# 06_DRIVER.net
KiCad netlist of a schematic drawn in Altium Designer
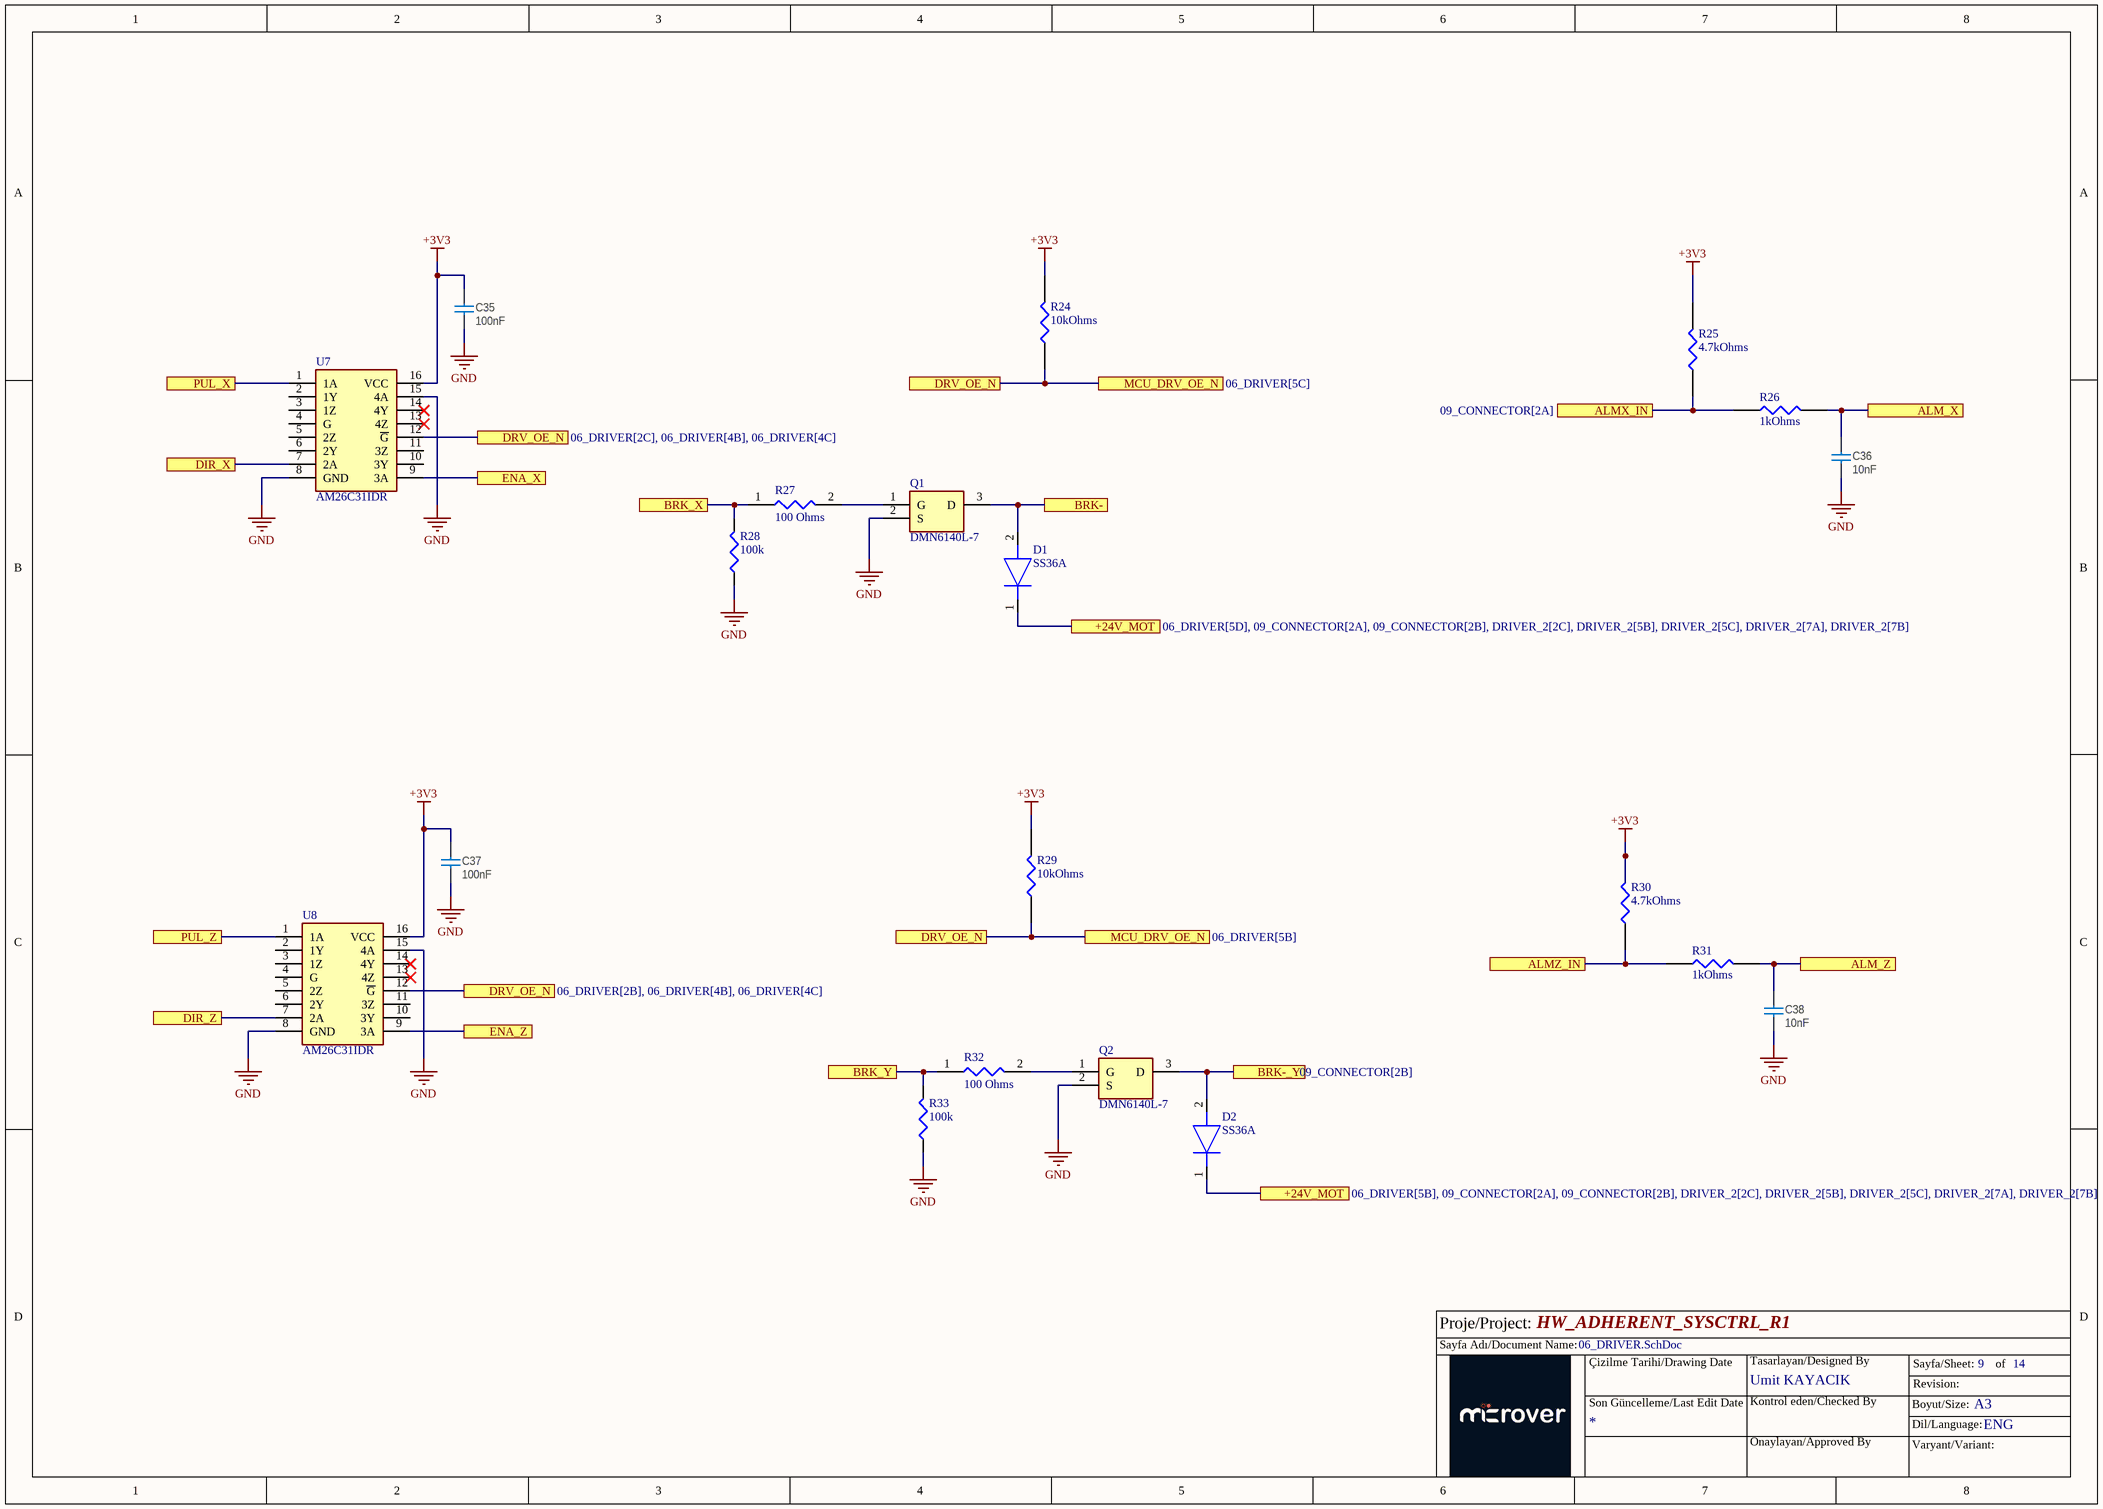
[diagram p0: 06_DRIVER.SchDoc]

(export (version "E")
  (design (tool "Eeschema 10.0.6"))
  (components
    (comp (ref "C35")
      (value "100nF")
      (footprint "CAPC0603X03L_C")
      (description "Capacitor, X5R, ±10%")
      (fields
        (field (name "PART NUMBER") "C0201-100n")
        (field (name "MANUFACTURER") "N.A.")
        (field (name "AUTHOR") "rsk")
      )
      (libsource (lib "HW_ADHERENT_SYSCTRL_R1_L1") (part "C0201-100n"))
    )
    (comp (ref "C36")
      (value "10nF")
      (footprint "CAPC0603X03L_C")
      (description "Capacitor, X7R, ±10%")
      (fields
        (field (name "PART NUMBER") "C0201-10n")
        (field (name "MANUFACTURER") "N.A.")
        (field (name "AUTHOR") "rsk")
      )
      (libsource (lib "HW_ADHERENT_SYSCTRL_R1_L1") (part "C0201-10n"))
    )
    (comp (ref "C37")
      (value "100nF")
      (footprint "CAPC0603X03L_C")
      (description "Capacitor, X5R, ±10%")
      (fields
        (field (name "PART NUMBER") "C0201-100n")
        (field (name "MANUFACTURER") "N.A.")
        (field (name "AUTHOR") "rsk")
      )
      (libsource (lib "HW_ADHERENT_SYSCTRL_R1_L1") (part "C0201-100n"))
    )
    (comp (ref "C38")
      (value "10nF")
      (footprint "CAPC0603X03L_C")
      (description "Capacitor, X7R, ±10%")
      (fields
        (field (name "PART NUMBER") "C0201-10n")
        (field (name "MANUFACTURER") "N.A.")
        (field (name "AUTHOR") "rsk")
      )
      (libsource (lib "HW_ADHERENT_SYSCTRL_R1_L1") (part "C0201-10n"))
    )
    (comp (ref "D1")
      (value "SS36A")
      (footprint "SamacSys:DIOM5026X262N")
      (description "Diode")
      (libsource (lib "*") (part "SS36A"))
    )
    (comp (ref "D2")
      (value "SS36A")
      (footprint "SamacSys:DIOM5026X262N")
      (description "Diode")
      (libsource (lib "*") (part "SS36A"))
    )
    (comp (ref "Q1")
      (value "DMN6140L-7")
      (footprint "SamacSys:SOT96P240X110-3N")
      (description "Transistor")
      (fields (field (name "MOUSER PART NUMBER") "621-DMN6140L-7"))
      (libsource (lib "*") (part "DMN6140L-7"))
    )
    (comp (ref "Q2")
      (value "DMN6140L-7")
      (footprint "SamacSys:SOT96P240X110-3N")
      (description "Transistor")
      (fields (field (name "MOUSER PART NUMBER") "621-DMN6140L-7"))
      (libsource (lib "*") (part "DMN6140L-7"))
    )
    (comp (ref "R24")
      (value "10kOhms")
      (footprint "RESC0603X03L_C")
      (description "10 kOhms ±1% 0.1W, 1/10W Chip Resistor 0603 (1608 Metric) Automotive AEC-Q200 Thin Film")
      (fields (field (name "MANUFACTURER") "Vishay Dale"))
      (libsource (lib "HW_ADHERENT_SYSCTRL_R1_L1") (part "TNPW060310K0FHTA"))
    )
    (comp (ref "R25")
      (value "4.7kOhms")
      (footprint "RES_0402")
      (description "RES SMD 4.7K OHM 1% 1/16W 0402")
      (fields
        (field (name "MANUFACTURER") "Yageo Group")
        (field (name "MANUFACTURER PART NUMBER") "RT0402FRE074K7L")
      )
      (libsource (lib "HW_ADHERENT_SYSCTRL_R1_L1") (part "RT0402FRE074K7L"))
    )
    (comp (ref "R26")
      (value "1kOhms")
      (footprint "RESC0603X03L_C")
      (description "RES SMD 1K OHM 0.1% 1/16W 0603")
      (fields
        (field (name "MANUFACTURER") "TE Connectivity")
        (field (name "MANUFACTURER PART NUMBER") "CPF0603B1K0E")
      )
      (libsource (lib "HW_ADHERENT_SYSCTRL_R1_L1") (part "CPF0603B1K0E"))
    )
    (comp (ref "R27")
      (value "100 Ohms")
      (footprint "SamacSys:RESC1608X55N")
      (description "Resistor")
      (fields (field (name "MANUFACTURER_PART_NUMBER") "RC0603JR07100RL"))
      (libsource (lib "SamacSys") (part "RC0603JR07100RL"))
    )
    (comp (ref "R28")
      (value "100k")
      (footprint "SMR0603")
      (description "100 kOhms ±1% 0.1W, 1/10W Chip Resistor 0603 (1608 Metric) Moisture Resistant Thick Film")
      (fields
        (field (name "MANUFACTURER PART NUMBER") "RC0603FR-07100KL")
        (field (name "LCSC PART NUMBER") "C123419")
      )
      (libsource (lib "HW_ADHERENT_SYSCTRL_R1_L2") (part "RES0603_100K_%1"))
    )
    (comp (ref "R29")
      (value "10kOhms")
      (footprint "RESC0603X03L_C")
      (description "10 kOhms ±1% 0.1W, 1/10W Chip Resistor 0603 (1608 Metric) Automotive AEC-Q200 Thin Film")
      (fields (field (name "MANUFACTURER") "Vishay Dale"))
      (libsource (lib "HW_ADHERENT_SYSCTRL_R1_L1") (part "TNPW060310K0FHTA"))
    )
    (comp (ref "R30")
      (value "4.7kOhms")
      (footprint "RES_0402")
      (description "RES SMD 4.7K OHM 1% 1/16W 0402")
      (fields
        (field (name "MANUFACTURER") "Yageo Group")
        (field (name "MANUFACTURER PART NUMBER") "RT0402FRE074K7L")
      )
      (libsource (lib "HW_ADHERENT_SYSCTRL_R1_L1") (part "RT0402FRE074K7L"))
    )
    (comp (ref "R31")
      (value "1kOhms")
      (footprint "RESC0603X03L_C")
      (description "RES SMD 1K OHM 0.1% 1/16W 0603")
      (fields
        (field (name "MANUFACTURER") "TE Connectivity")
        (field (name "MANUFACTURER PART NUMBER") "CPF0603B1K0E")
      )
      (libsource (lib "HW_ADHERENT_SYSCTRL_R1_L1") (part "CPF0603B1K0E"))
    )
    (comp (ref "R32")
      (value "100 Ohms")
      (footprint "SamacSys:RESC1608X55N")
      (description "Resistor")
      (fields (field (name "MANUFACTURER_PART_NUMBER") "RC0603JR07100RL"))
      (libsource (lib "SamacSys") (part "RC0603JR07100RL"))
    )
    (comp (ref "R33")
      (value "100k")
      (footprint "SMR0603")
      (description "100 kOhms ±1% 0.1W, 1/10W Chip Resistor 0603 (1608 Metric) Moisture Resistant Thick Film")
      (fields
        (field (name "MANUFACTURER PART NUMBER") "RC0603FR-07100KL")
        (field (name "LCSC PART NUMBER") "C123419")
      )
      (libsource (lib "HW_ADHERENT_SYSCTRL_R1_L2") (part "RES0603_100K_%1"))
    )
    (comp (ref "U7")
      (value "AM26C31IDR")
      (footprint "SOIC127P600X175-16N")
      (description "4/0 Driver 16-SOIC")
      (fields (field (name "MANUFACTURER") "Texas Instruments"))
      (libsource (lib "HW_ADHERENT_SYSCTRL_R1_L1") (part "AM26C31IDR"))
    )
    (comp (ref "U8")
      (value "AM26C31IDR")
      (footprint "SOIC127P600X175-16N")
      (description "4/0 Driver 16-SOIC")
      (fields (field (name "MANUFACTURER") "Texas Instruments"))
      (libsource (lib "HW_ADHERENT_SYSCTRL_R1_L1") (part "AM26C31IDR"))
    )
  )
  (nets
    (net (code "1") (name "+3V3") (class "Default")
      (node (ref "C35") (pin "2") (pinfunction "2_2") (pintype "passive"))
      (node (ref "C37") (pin "2") (pinfunction "2_2") (pintype "passive"))
      (node (ref "R24") (pin "2") (pinfunction "2_2") (pintype "passive"))
      (node (ref "R25") (pin "2") (pinfunction "2_2") (pintype "passive"))
      (node (ref "R29") (pin "2") (pinfunction "2_2") (pintype "passive"))
      (node (ref "R30") (pin "2") (pinfunction "2_2") (pintype "passive"))
      (node (ref "U7") (pin "16") (pinfunction "VCC_16") (pintype "passive"))
      (node (ref "U8") (pin "16") (pinfunction "VCC_16") (pintype "passive"))
    )
    (net (code "2") (name "/+24V_MOT") (class "Default")
      (node (ref "D1") (pin "1") (pinfunction "K_1") (pintype "passive"))
      (node (ref "D2") (pin "1") (pinfunction "K_1") (pintype "passive"))
    )
    (net (code "3") (name "/ALMX_IN") (class "Default")
      (node (ref "R25") (pin "1") (pinfunction "1_1") (pintype "passive"))
      (node (ref "R26") (pin "1") (pinfunction "1_1") (pintype "passive"))
    )
    (net (code "4") (name "/ALMZ_IN") (class "Default")
      (node (ref "R30") (pin "1") (pinfunction "1_1") (pintype "passive"))
      (node (ref "R31") (pin "1") (pinfunction "1_1") (pintype "passive"))
    )
    (net (code "5") (name "/ALM_X") (class "Default")
      (node (ref "C36") (pin "2") (pinfunction "2_2") (pintype "passive"))
      (node (ref "R26") (pin "2") (pinfunction "2_2") (pintype "passive"))
    )
    (net (code "6") (name "/ALM_Z") (class "Default")
      (node (ref "C38") (pin "2") (pinfunction "2_2") (pintype "passive"))
      (node (ref "R31") (pin "2") (pinfunction "2_2") (pintype "passive"))
    )
    (net (code "7") (name "/BRK-") (class "Default")
      (node (ref "D1") (pin "2") (pinfunction "A_2") (pintype "passive"))
      (node (ref "Q1") (pin "3") (pinfunction "D_3") (pintype "passive"))
    )
    (net (code "8") (name "/BRK-_Y") (class "Default")
      (node (ref "D2") (pin "2") (pinfunction "A_2") (pintype "passive"))
      (node (ref "Q2") (pin "3") (pinfunction "D_3") (pintype "passive"))
    )
    (net (code "9") (name "/BRK_X") (class "Default")
      (node (ref "R27") (pin "1") (pinfunction "1_1") (pintype "passive"))
      (node (ref "R28") (pin "2") (pinfunction "2_2") (pintype "passive"))
    )
    (net (code "10") (name "/BRK_Y") (class "Default")
      (node (ref "R32") (pin "1") (pinfunction "1_1") (pintype "passive"))
      (node (ref "R33") (pin "2") (pinfunction "2_2") (pintype "passive"))
    )
    (net (code "11") (name "/DIR_X") (class "Default")
      (node (ref "U7") (pin "7") (pinfunction "2A_7") (pintype "passive"))
    )
    (net (code "12") (name "/DIR_Z") (class "Default")
      (node (ref "U8") (pin "7") (pinfunction "2A_7") (pintype "passive"))
    )
    (net (code "13") (name "/DRV_OE_N") (class "Default")
      (node (ref "R24") (pin "1") (pinfunction "1_1") (pintype "passive"))
      (node (ref "R29") (pin "1") (pinfunction "1_1") (pintype "passive"))
      (node (ref "U7") (pin "12") (pinfunction "~{G}_12") (pintype "passive"))
      (node (ref "U8") (pin "12") (pinfunction "~{G}_12") (pintype "passive"))
    )
    (net (code "14") (name "/ENA_X") (class "Default")
      (node (ref "U7") (pin "9") (pinfunction "3A_9") (pintype "passive"))
    )
    (net (code "15") (name "/ENA_Z") (class "Default")
      (node (ref "U8") (pin "9") (pinfunction "3A_9") (pintype "passive"))
    )
    (net (code "16") (name "/PUL_X") (class "Default")
      (node (ref "U7") (pin "1") (pinfunction "1A_1") (pintype "passive"))
    )
    (net (code "17") (name "/PUL_Z") (class "Default")
      (node (ref "U8") (pin "1") (pinfunction "1A_1") (pintype "passive"))
    )
    (net (code "18") (name "GND") (class "Default")
      (node (ref "C35") (pin "1") (pinfunction "1_1") (pintype "passive"))
      (node (ref "C36") (pin "1") (pinfunction "1_1") (pintype "passive"))
      (node (ref "C37") (pin "1") (pinfunction "1_1") (pintype "passive"))
      (node (ref "C38") (pin "1") (pinfunction "1_1") (pintype "passive"))
      (node (ref "Q1") (pin "2") (pinfunction "S_2") (pintype "passive"))
      (node (ref "Q2") (pin "2") (pinfunction "S_2") (pintype "passive"))
      (node (ref "R28") (pin "1") (pinfunction "1_1") (pintype "passive"))
      (node (ref "R33") (pin "1") (pinfunction "1_1") (pintype "passive"))
      (node (ref "U7") (pin "15") (pinfunction "4A_15") (pintype "passive"))
      (node (ref "U7") (pin "8") (pinfunction "GND_8") (pintype "passive"))
      (node (ref "U8") (pin "15") (pinfunction "4A_15") (pintype "passive"))
      (node (ref "U8") (pin "8") (pinfunction "GND_8") (pintype "passive"))
    )
    (net (code "19") (name "Net-(Q1-G)") (class "Default")
      (node (ref "Q1") (pin "1") (pinfunction "G_1") (pintype "passive"))
      (node (ref "R27") (pin "2") (pinfunction "2_2") (pintype "passive"))
    )
    (net (code "20") (name "Net-(Q2-G)") (class "Default")
      (node (ref "Q2") (pin "1") (pinfunction "G_1") (pintype "passive"))
      (node (ref "R32") (pin "2") (pinfunction "2_2") (pintype "passive"))
    )
    (net (code "21") (name "unconnected-(U7-1Y-Pad2)") (class "Default")
      (node (ref "U7") (pin "2") (pinfunction "1Y_2") (pintype "passive"))
    )
    (net (code "22") (name "unconnected-(U7-1Z-Pad3)") (class "Default")
      (node (ref "U7") (pin "3") (pinfunction "1Z_3") (pintype "passive"))
    )
    (net (code "23") (name "unconnected-(U7-2Y-Pad6)") (class "Default")
      (node (ref "U7") (pin "6") (pinfunction "2Y_6") (pintype "passive"))
    )
    (net (code "24") (name "unconnected-(U7-2Z-Pad5)") (class "Default")
      (node (ref "U7") (pin "5") (pinfunction "2Z_5") (pintype "passive"))
    )
    (net (code "25") (name "unconnected-(U7-3Y-Pad10)") (class "Default")
      (node (ref "U7") (pin "10") (pinfunction "3Y_10") (pintype "passive"))
    )
    (net (code "26") (name "unconnected-(U7-3Z-Pad11)") (class "Default")
      (node (ref "U7") (pin "11") (pinfunction "3Z_11") (pintype "passive"))
    )
    (net (code "27") (name "unconnected-(U7-4Y-Pad14)") (class "Default")
      (node (ref "U7") (pin "14") (pinfunction "4Y_14") (pintype "passive+no_connect"))
    )
    (net (code "28") (name "unconnected-(U7-4Z-Pad13)") (class "Default")
      (node (ref "U7") (pin "13") (pinfunction "4Z_13") (pintype "passive+no_connect"))
    )
    (net (code "29") (name "unconnected-(U7-G-Pad4)") (class "Default")
      (node (ref "U7") (pin "4") (pinfunction "G_4") (pintype "passive"))
    )
    (net (code "30") (name "unconnected-(U8-1Y-Pad2)") (class "Default")
      (node (ref "U8") (pin "2") (pinfunction "1Y_2") (pintype "passive"))
    )
    (net (code "31") (name "unconnected-(U8-1Z-Pad3)") (class "Default")
      (node (ref "U8") (pin "3") (pinfunction "1Z_3") (pintype "passive"))
    )
    (net (code "32") (name "unconnected-(U8-2Y-Pad6)") (class "Default")
      (node (ref "U8") (pin "6") (pinfunction "2Y_6") (pintype "passive"))
    )
    (net (code "33") (name "unconnected-(U8-2Z-Pad5)") (class "Default")
      (node (ref "U8") (pin "5") (pinfunction "2Z_5") (pintype "passive"))
    )
    (net (code "34") (name "unconnected-(U8-3Y-Pad10)") (class "Default")
      (node (ref "U8") (pin "10") (pinfunction "3Y_10") (pintype "passive"))
    )
    (net (code "35") (name "unconnected-(U8-3Z-Pad11)") (class "Default")
      (node (ref "U8") (pin "11") (pinfunction "3Z_11") (pintype "passive"))
    )
    (net (code "36") (name "unconnected-(U8-4Y-Pad14)") (class "Default")
      (node (ref "U8") (pin "14") (pinfunction "4Y_14") (pintype "passive+no_connect"))
    )
    (net (code "37") (name "unconnected-(U8-4Z-Pad13)") (class "Default")
      (node (ref "U8") (pin "13") (pinfunction "4Z_13") (pintype "passive+no_connect"))
    )
    (net (code "38") (name "unconnected-(U8-G-Pad4)") (class "Default")
      (node (ref "U8") (pin "4") (pinfunction "G_4") (pintype "passive"))
    )
  )
)
